# SensorPlatine.net
KiCad netlist of a schematic drawn in EAGLE
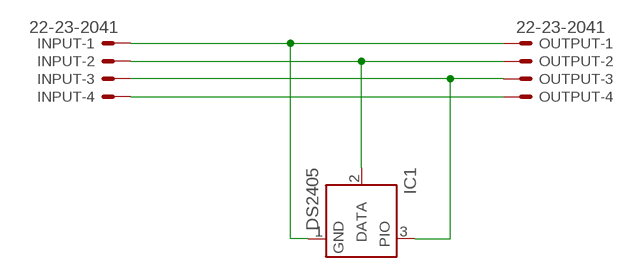
[diagram p0: schematic, sheet 1]

(export (version "E")
  (design (tool "Eeschema 10.0.6"))
  (components
    (comp (ref "IC1")
      (value "DS2405")
      (footprint "eagle-import:TO92-")
      (fields (field (name "MF") "DALLAS SEMICONDUCTOR"))
      (libsource (lib "eagle-import") (part "DS2405"))
    )
    (comp (ref "INPUT")
      (value "22-23-2041")
      (footprint "eagle-import:22-23-2041")
      (fields (field (name "MF") "MOLEX"))
      (libsource (lib "eagle-import") (part "22-23-2041"))
    )
    (comp (ref "OUTPUT")
      (value "22-23-2041")
      (footprint "eagle-import:22-23-2041")
      (fields (field (name "MF") "MOLEX"))
      (libsource (lib "eagle-import") (part "22-23-2041"))
    )
  )
  (nets
    (net (code "1") (name "Net-(IC1-DATA)") (class "Default")
      (node (ref "IC1") (pin "2") (pinfunction "DATA_2") (pintype "input"))
      (node (ref "INPUT") (pin "2") (pinfunction "S_2") (pintype "passive"))
      (node (ref "OUTPUT") (pin "2") (pinfunction "S_2") (pintype "passive"))
    )
    (net (code "2") (name "Net-(IC1-GND)") (class "Default")
      (node (ref "IC1") (pin "1") (pinfunction "GND_1") (pintype "passive"))
      (node (ref "INPUT") (pin "1") (pinfunction "S_1") (pintype "passive"))
      (node (ref "OUTPUT") (pin "1") (pinfunction "S_1") (pintype "passive"))
    )
    (net (code "3") (name "Net-(IC1-PIO)") (class "Default")
      (node (ref "IC1") (pin "3") (pinfunction "PIO_3") (pintype "passive"))
      (node (ref "INPUT") (pin "3") (pinfunction "S_3") (pintype "passive"))
      (node (ref "OUTPUT") (pin "3") (pinfunction "S_3") (pintype "passive"))
    )
    (net (code "4") (name "Net-(INPUTD-S)") (class "Default")
      (node (ref "INPUT") (pin "4") (pinfunction "S_4") (pintype "passive"))
      (node (ref "OUTPUT") (pin "4") (pinfunction "S_4") (pintype "passive"))
    )
  )
)
